# encoder_board.net
KiCad netlist of a schematic drawn in EAGLE
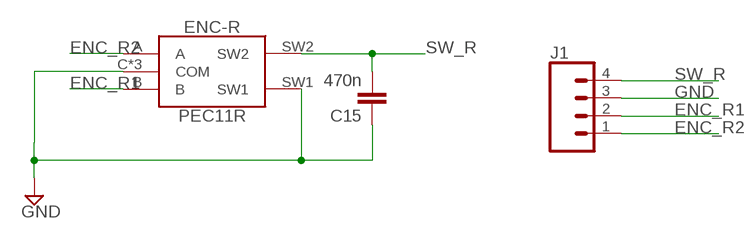
[diagram p0: schematic, sheet 1]

(export (version "E")
  (design (tool "Eeschema 10.0.6"))
  (components
    (comp (ref "C15")
      (value "470n")
      (footprint "eagle-import:C0603")
      (libsource (lib "eagle-import") (part "C-EUC0603"))
    )
    (comp (ref "ENC-R")
      (value "PEC11R")
      (footprint "eagle-import:PEC11R-4XXXK-SXXXX")
      (fields
        (field (name "ARROW_PART_NUMBER") "PEC11R-4215K-S0024")
        (field (name "RS_PART_NUMBER") "1674651")
      )
      (libsource (lib "eagle-import") (part "PEC11R"))
    )
    (comp (ref "J1")
      (value "CONN_04LOCK")
      (footprint "eagle-import:1X04_LOCK")
      (libsource (lib "eagle-import") (part "CONN_04LOCK"))
    )
  )
  (nets
    (net (code "1") (name "/ENC_R1") (class "Default")
      (node (ref "ENC-R") (pin "B") (pinfunction "B_B") (pintype "bidirectional"))
      (node (ref "J1") (pin "2") (pinfunction "2_2") (pintype "passive"))
    )
    (net (code "2") (name "/ENC_R2") (class "Default")
      (node (ref "ENC-R") (pin "A") (pinfunction "A_A") (pintype "bidirectional"))
      (node (ref "J1") (pin "1") (pinfunction "1_1") (pintype "passive"))
    )
    (net (code "3") (name "/SW_R") (class "Default")
      (node (ref "C15") (pin "2") (pinfunction "2_2") (pintype "passive"))
      (node (ref "ENC-R") (pin "SW2") (pinfunction "SW2_SW2") (pintype "bidirectional"))
      (node (ref "J1") (pin "4") (pinfunction "4_4") (pintype "passive"))
    )
    (net (code "4") (name "GND") (class "Default")
      (node (ref "C15") (pin "1") (pinfunction "1_1") (pintype "passive"))
      (node (ref "ENC-R") (pin "C") (pinfunction "COM_C") (pintype "bidirectional"))
      (node (ref "ENC-R") (pin "SH1") (pinfunction "COM_SH1") (pintype "bidirectional"))
      (node (ref "ENC-R") (pin "SH2") (pinfunction "COM_SH2") (pintype "bidirectional"))
      (node (ref "ENC-R") (pin "SW1") (pinfunction "SW1_SW1") (pintype "bidirectional"))
      (node (ref "J1") (pin "3") (pinfunction "3_3") (pintype "passive"))
    )
  )
)
